# circuit.net
KiCad netlist of a schematic drawn in EAGLE
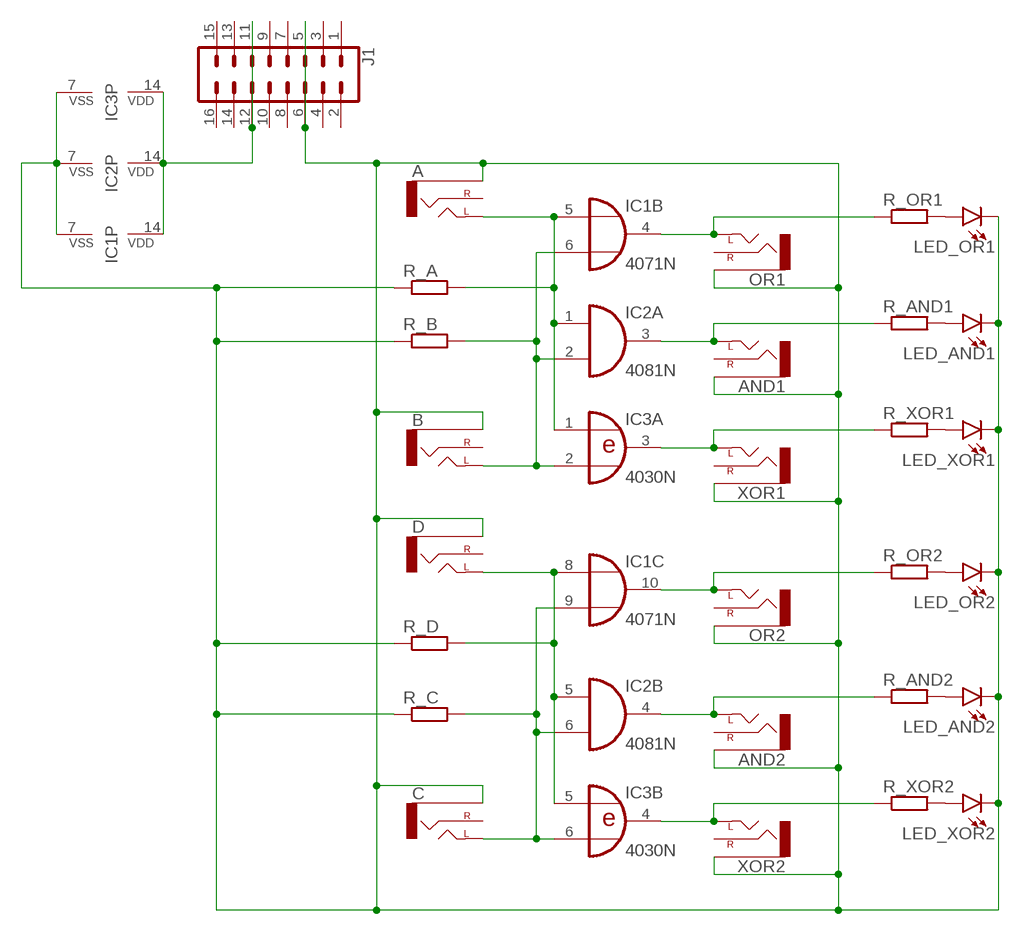
[diagram p0: schematic, sheet 1]

(export (version "E")
  (design (tool "Eeschema 10.0.6"))
  (components
    (comp (ref "A")
      (value "THONKI-STEREO")
      (footprint "eagle-import:WQP-PJ366ST_JACK")
      (libsource (lib "eagle-import") (part "THONKI-STEREO"))
    )
    (comp (ref "AND1")
      (value "THONKI-STEREO")
      (footprint "eagle-import:WQP-PJ366ST_JACK")
      (libsource (lib "eagle-import") (part "THONKI-STEREO"))
    )
    (comp (ref "AND2")
      (value "THONKI-STEREO")
      (footprint "eagle-import:WQP-PJ366ST_JACK")
      (libsource (lib "eagle-import") (part "THONKI-STEREO"))
    )
    (comp (ref "B")
      (value "THONKI-STEREO")
      (footprint "eagle-import:WQP-PJ366ST_JACK")
      (libsource (lib "eagle-import") (part "THONKI-STEREO"))
    )
    (comp (ref "C")
      (value "THONKI-STEREO")
      (footprint "eagle-import:WQP-PJ366ST_JACK")
      (libsource (lib "eagle-import") (part "THONKI-STEREO"))
    )
    (comp (ref "D")
      (value "THONKI-STEREO")
      (footprint "eagle-import:WQP-PJ366ST_JACK")
      (libsource (lib "eagle-import") (part "THONKI-STEREO"))
    )
    (comp (ref "IC1")
      (value "4071N")
      (footprint "eagle-import:DIL14")
      (libsource (lib "eagle-import") (part "4071N"))
    )
    (comp (ref "IC2")
      (value "4081N")
      (footprint "eagle-import:DIL14")
      (libsource (lib "eagle-import") (part "4081N"))
    )
    (comp (ref "IC3")
      (value "4030N")
      (footprint "eagle-import:DIL14")
      (libsource (lib "eagle-import") (part "4030N"))
    )
    (comp (ref "J1")
      (value "CONN_08X2")
      (footprint "eagle-import:2X8")
      (libsource (lib "eagle-import") (part "CONN_08X2"))
    )
    (comp (ref "LED_AND1")
      (value "LED3MM")
      (footprint "eagle-import:LED_3MM")
      (libsource (lib "eagle-import") (part "LED3MM"))
    )
    (comp (ref "LED_AND2")
      (value "LED3MM")
      (footprint "eagle-import:LED_3MM")
      (libsource (lib "eagle-import") (part "LED3MM"))
    )
    (comp (ref "LED_OR1")
      (value "LED3MM")
      (footprint "eagle-import:LED_3MM")
      (libsource (lib "eagle-import") (part "LED3MM"))
    )
    (comp (ref "LED_OR2")
      (value "LED3MM")
      (footprint "eagle-import:LED_3MM")
      (libsource (lib "eagle-import") (part "LED3MM"))
    )
    (comp (ref "LED_XOR1")
      (value "LED3MM")
      (footprint "eagle-import:LED_3MM")
      (libsource (lib "eagle-import") (part "LED3MM"))
    )
    (comp (ref "LED_XOR2")
      (value "LED3MM")
      (footprint "eagle-import:LED_3MM")
      (libsource (lib "eagle-import") (part "LED3MM"))
    )
    (comp (ref "OR1")
      (value "THONKI-STEREO")
      (footprint "eagle-import:WQP-PJ366ST_JACK")
      (libsource (lib "eagle-import") (part "THONKI-STEREO"))
    )
    (comp (ref "OR2")
      (value "THONKI-STEREO")
      (footprint "eagle-import:WQP-PJ366ST_JACK")
      (libsource (lib "eagle-import") (part "THONKI-STEREO"))
    )
    (comp (ref "R_A")
      (value "RESISTOR7MM")
      (footprint "eagle-import:7MM_RESISTOR")
      (libsource (lib "eagle-import") (part "RESISTOR7MM"))
    )
    (comp (ref "R_AND1")
      (value "RESISTOR7MM")
      (footprint "eagle-import:7MM_RESISTOR")
      (libsource (lib "eagle-import") (part "RESISTOR7MM"))
    )
    (comp (ref "R_AND2")
      (value "RESISTOR7MM")
      (footprint "eagle-import:7MM_RESISTOR")
      (libsource (lib "eagle-import") (part "RESISTOR7MM"))
    )
    (comp (ref "R_B")
      (value "RESISTOR7MM")
      (footprint "eagle-import:7MM_RESISTOR")
      (libsource (lib "eagle-import") (part "RESISTOR7MM"))
    )
    (comp (ref "R_C")
      (value "RESISTOR7MM")
      (footprint "eagle-import:7MM_RESISTOR")
      (libsource (lib "eagle-import") (part "RESISTOR7MM"))
    )
    (comp (ref "R_D")
      (value "RESISTOR7MM")
      (footprint "eagle-import:7MM_RESISTOR")
      (libsource (lib "eagle-import") (part "RESISTOR7MM"))
    )
    (comp (ref "R_OR1")
      (value "RESISTOR7MM")
      (footprint "eagle-import:7MM_RESISTOR")
      (libsource (lib "eagle-import") (part "RESISTOR7MM"))
    )
    (comp (ref "R_OR2")
      (value "RESISTOR7MM")
      (footprint "eagle-import:7MM_RESISTOR")
      (libsource (lib "eagle-import") (part "RESISTOR7MM"))
    )
    (comp (ref "R_XOR1")
      (value "RESISTOR7MM")
      (footprint "eagle-import:7MM_RESISTOR")
      (libsource (lib "eagle-import") (part "RESISTOR7MM"))
    )
    (comp (ref "R_XOR2")
      (value "RESISTOR7MM")
      (footprint "eagle-import:7MM_RESISTOR")
      (libsource (lib "eagle-import") (part "RESISTOR7MM"))
    )
    (comp (ref "XOR1")
      (value "THONKI-STEREO")
      (footprint "eagle-import:WQP-PJ366ST_JACK")
      (libsource (lib "eagle-import") (part "THONKI-STEREO"))
    )
    (comp (ref "XOR2")
      (value "THONKI-STEREO")
      (footprint "eagle-import:WQP-PJ366ST_JACK")
      (libsource (lib "eagle-import") (part "THONKI-STEREO"))
    )
  )
  (nets
    (net (code "1") (name "Net-(A-LEFT)") (class "Default")
      (node (ref "A") (pin "P$1_TIP") (pinfunction "LEFT_P$1_TIP") (pintype "bidirectional"))
      (node (ref "IC1") (pin "5") (pinfunction "I0_5") (pintype "input"))
      (node (ref "IC2") (pin "1") (pinfunction "I0_1") (pintype "input"))
      (node (ref "IC3") (pin "1") (pinfunction "I0_1") (pintype "input"))
      (node (ref "R_A") (pin "2") (pinfunction "2_2") (pintype "passive"))
    )
    (net (code "2") (name "Net-(A-SLEEVE)") (class "Default")
      (node (ref "A") (pin "P$3_SLEEVE") (pinfunction "SLEEVE_P$3_SLEEVE") (pintype "bidirectional"))
      (node (ref "AND1") (pin "P$3_SLEEVE") (pinfunction "SLEEVE_P$3_SLEEVE") (pintype "bidirectional"))
      (node (ref "AND2") (pin "P$3_SLEEVE") (pinfunction "SLEEVE_P$3_SLEEVE") (pintype "bidirectional"))
      (node (ref "B") (pin "P$3_SLEEVE") (pinfunction "SLEEVE_P$3_SLEEVE") (pintype "bidirectional"))
      (node (ref "C") (pin "P$3_SLEEVE") (pinfunction "SLEEVE_P$3_SLEEVE") (pintype "bidirectional"))
      (node (ref "D") (pin "P$3_SLEEVE") (pinfunction "SLEEVE_P$3_SLEEVE") (pintype "bidirectional"))
      (node (ref "IC1") (pin "7") (pinfunction "VSS_7") (pintype "power_in"))
      (node (ref "IC2") (pin "7") (pinfunction "VSS_7") (pintype "power_in"))
      (node (ref "IC3") (pin "7") (pinfunction "VSS_7") (pintype "power_in"))
      (node (ref "J1") (pin "5") (pinfunction "5_5") (pintype "passive"))
      (node (ref "J1") (pin "6") (pinfunction "6_6") (pintype "passive"))
      (node (ref "LED_AND1") (pin "K") (pinfunction "C_K") (pintype "passive"))
      (node (ref "LED_AND2") (pin "K") (pinfunction "C_K") (pintype "passive"))
      (node (ref "LED_OR1") (pin "K") (pinfunction "C_K") (pintype "passive"))
      (node (ref "LED_OR2") (pin "K") (pinfunction "C_K") (pintype "passive"))
      (node (ref "LED_XOR1") (pin "K") (pinfunction "C_K") (pintype "passive"))
      (node (ref "LED_XOR2") (pin "K") (pinfunction "C_K") (pintype "passive"))
      (node (ref "OR1") (pin "P$3_SLEEVE") (pinfunction "SLEEVE_P$3_SLEEVE") (pintype "bidirectional"))
      (node (ref "OR2") (pin "P$3_SLEEVE") (pinfunction "SLEEVE_P$3_SLEEVE") (pintype "bidirectional"))
      (node (ref "R_A") (pin "1") (pinfunction "1_1") (pintype "passive"))
      (node (ref "R_B") (pin "1") (pinfunction "1_1") (pintype "passive"))
      (node (ref "R_C") (pin "1") (pinfunction "1_1") (pintype "passive"))
      (node (ref "R_D") (pin "1") (pinfunction "1_1") (pintype "passive"))
      (node (ref "XOR1") (pin "P$3_SLEEVE") (pinfunction "SLEEVE_P$3_SLEEVE") (pintype "bidirectional"))
      (node (ref "XOR2") (pin "P$3_SLEEVE") (pinfunction "SLEEVE_P$3_SLEEVE") (pintype "bidirectional"))
    )
    (net (code "3") (name "Net-(AND1-LEFT)") (class "Default")
      (node (ref "AND1") (pin "P$1_TIP") (pinfunction "LEFT_P$1_TIP") (pintype "bidirectional"))
      (node (ref "IC2") (pin "3") (pinfunction "O_3") (pintype "output"))
      (node (ref "R_AND1") (pin "1") (pinfunction "1_1") (pintype "passive"))
    )
    (net (code "4") (name "Net-(AND2-LEFT)") (class "Default")
      (node (ref "AND2") (pin "P$1_TIP") (pinfunction "LEFT_P$1_TIP") (pintype "bidirectional"))
      (node (ref "IC2") (pin "4") (pinfunction "O_4") (pintype "output"))
      (node (ref "R_AND2") (pin "1") (pinfunction "1_1") (pintype "passive"))
    )
    (net (code "5") (name "Net-(B-LEFT)") (class "Default")
      (node (ref "B") (pin "P$1_TIP") (pinfunction "LEFT_P$1_TIP") (pintype "bidirectional"))
      (node (ref "IC1") (pin "6") (pinfunction "I1_6") (pintype "input"))
      (node (ref "IC2") (pin "2") (pinfunction "I1_2") (pintype "input"))
      (node (ref "IC3") (pin "2") (pinfunction "I1_2") (pintype "input"))
      (node (ref "R_B") (pin "2") (pinfunction "2_2") (pintype "passive"))
    )
    (net (code "6") (name "Net-(C-LEFT)") (class "Default")
      (node (ref "C") (pin "P$1_TIP") (pinfunction "LEFT_P$1_TIP") (pintype "bidirectional"))
      (node (ref "IC1") (pin "9") (pinfunction "I1_9") (pintype "input"))
      (node (ref "IC2") (pin "6") (pinfunction "I1_6") (pintype "input"))
      (node (ref "IC3") (pin "6") (pinfunction "I1_6") (pintype "input"))
      (node (ref "R_C") (pin "2") (pinfunction "2_2") (pintype "passive"))
    )
    (net (code "7") (name "Net-(D-LEFT)") (class "Default")
      (node (ref "D") (pin "P$1_TIP") (pinfunction "LEFT_P$1_TIP") (pintype "bidirectional"))
      (node (ref "IC1") (pin "8") (pinfunction "I0_8") (pintype "input"))
      (node (ref "IC2") (pin "5") (pinfunction "I0_5") (pintype "input"))
      (node (ref "IC3") (pin "5") (pinfunction "I0_5") (pintype "input"))
      (node (ref "R_D") (pin "2") (pinfunction "2_2") (pintype "passive"))
    )
    (net (code "8") (name "Net-(IC1B-O)") (class "Default")
      (node (ref "IC1") (pin "4") (pinfunction "O_4") (pintype "output"))
      (node (ref "OR1") (pin "P$1_TIP") (pinfunction "LEFT_P$1_TIP") (pintype "bidirectional"))
      (node (ref "R_OR1") (pin "1") (pinfunction "1_1") (pintype "passive"))
    )
    (net (code "9") (name "Net-(IC1C-O)") (class "Default")
      (node (ref "IC1") (pin "10") (pinfunction "O_10") (pintype "output"))
      (node (ref "OR2") (pin "P$1_TIP") (pinfunction "LEFT_P$1_TIP") (pintype "bidirectional"))
      (node (ref "R_OR2") (pin "1") (pinfunction "1_1") (pintype "passive"))
    )
    (net (code "10") (name "Net-(IC1E-VDD)") (class "Default")
      (node (ref "IC1") (pin "14") (pinfunction "VDD_14") (pintype "power_in"))
      (node (ref "IC2") (pin "14") (pinfunction "VDD_14") (pintype "power_in"))
      (node (ref "IC3") (pin "14") (pinfunction "VDD_14") (pintype "power_in"))
      (node (ref "J1") (pin "11") (pinfunction "11_11") (pintype "passive"))
      (node (ref "J1") (pin "12") (pinfunction "12_12") (pintype "passive"))
    )
    (net (code "11") (name "Net-(IC3A-O)") (class "Default")
      (node (ref "IC3") (pin "3") (pinfunction "O_3") (pintype "output"))
      (node (ref "R_XOR1") (pin "1") (pinfunction "1_1") (pintype "passive"))
      (node (ref "XOR1") (pin "P$1_TIP") (pinfunction "LEFT_P$1_TIP") (pintype "bidirectional"))
    )
    (net (code "12") (name "Net-(IC3B-O)") (class "Default")
      (node (ref "IC3") (pin "4") (pinfunction "O_4") (pintype "output"))
      (node (ref "R_XOR2") (pin "1") (pinfunction "1_1") (pintype "passive"))
      (node (ref "XOR2") (pin "P$1_TIP") (pinfunction "LEFT_P$1_TIP") (pintype "bidirectional"))
    )
    (net (code "13") (name "Net-(LED_AND1-PadA)") (class "Default")
      (node (ref "LED_AND1") (pin "A") (pinfunction "A_A") (pintype "passive"))
      (node (ref "R_AND1") (pin "2") (pinfunction "2_2") (pintype "passive"))
    )
    (net (code "14") (name "Net-(LED_AND2-PadA)") (class "Default")
      (node (ref "LED_AND2") (pin "A") (pinfunction "A_A") (pintype "passive"))
      (node (ref "R_AND2") (pin "2") (pinfunction "2_2") (pintype "passive"))
    )
    (net (code "15") (name "Net-(LED_OR1-PadA)") (class "Default")
      (node (ref "LED_OR1") (pin "A") (pinfunction "A_A") (pintype "passive"))
      (node (ref "R_OR1") (pin "2") (pinfunction "2_2") (pintype "passive"))
    )
    (net (code "16") (name "Net-(LED_OR2-PadA)") (class "Default")
      (node (ref "LED_OR2") (pin "A") (pinfunction "A_A") (pintype "passive"))
      (node (ref "R_OR2") (pin "2") (pinfunction "2_2") (pintype "passive"))
    )
    (net (code "17") (name "Net-(LED_XOR1-PadA)") (class "Default")
      (node (ref "LED_XOR1") (pin "A") (pinfunction "A_A") (pintype "passive"))
      (node (ref "R_XOR1") (pin "2") (pinfunction "2_2") (pintype "passive"))
    )
    (net (code "18") (name "Net-(LED_XOR2-PadA)") (class "Default")
      (node (ref "LED_XOR2") (pin "A") (pinfunction "A_A") (pintype "passive"))
      (node (ref "R_XOR2") (pin "2") (pinfunction "2_2") (pintype "passive"))
    )
    (net (code "19") (name "unconnected-(A-RIGHT-PadP$2_SWITCH)") (class "Default")
      (node (ref "A") (pin "P$2_SWITCH") (pinfunction "RIGHT_P$2_SWITCH") (pintype "bidirectional"))
    )
    (net (code "20") (name "unconnected-(AND1-RIGHT-PadP$2_SWITCH)") (class "Default")
      (node (ref "AND1") (pin "P$2_SWITCH") (pinfunction "RIGHT_P$2_SWITCH") (pintype "bidirectional"))
    )
    (net (code "21") (name "unconnected-(AND2-RIGHT-PadP$2_SWITCH)") (class "Default")
      (node (ref "AND2") (pin "P$2_SWITCH") (pinfunction "RIGHT_P$2_SWITCH") (pintype "bidirectional"))
    )
    (net (code "22") (name "unconnected-(B-RIGHT-PadP$2_SWITCH)") (class "Default")
      (node (ref "B") (pin "P$2_SWITCH") (pinfunction "RIGHT_P$2_SWITCH") (pintype "bidirectional"))
    )
    (net (code "23") (name "unconnected-(C-RIGHT-PadP$2_SWITCH)") (class "Default")
      (node (ref "C") (pin "P$2_SWITCH") (pinfunction "RIGHT_P$2_SWITCH") (pintype "bidirectional"))
    )
    (net (code "24") (name "unconnected-(D-RIGHT-PadP$2_SWITCH)") (class "Default")
      (node (ref "D") (pin "P$2_SWITCH") (pinfunction "RIGHT_P$2_SWITCH") (pintype "bidirectional"))
    )
    (net (code "25") (name "unconnected-(J1-Pad1)") (class "Default")
      (node (ref "J1") (pin "1") (pinfunction "1_1") (pintype "passive"))
    )
    (net (code "26") (name "unconnected-(J1-Pad2)") (class "Default")
      (node (ref "J1") (pin "2") (pinfunction "2_2") (pintype "passive"))
    )
    (net (code "27") (name "unconnected-(J1-Pad3)") (class "Default")
      (node (ref "J1") (pin "3") (pinfunction "3_3") (pintype "passive"))
    )
    (net (code "28") (name "unconnected-(J1-Pad4)") (class "Default")
      (node (ref "J1") (pin "4") (pinfunction "4_4") (pintype "passive"))
    )
    (net (code "29") (name "unconnected-(J1-Pad7)") (class "Default")
      (node (ref "J1") (pin "7") (pinfunction "7_7") (pintype "passive"))
    )
    (net (code "30") (name "unconnected-(J1-Pad8)") (class "Default")
      (node (ref "J1") (pin "8") (pinfunction "8_8") (pintype "passive"))
    )
    (net (code "31") (name "unconnected-(J1-Pad9)") (class "Default")
      (node (ref "J1") (pin "9") (pinfunction "9_9") (pintype "passive"))
    )
    (net (code "32") (name "unconnected-(J1-Pad10)") (class "Default")
      (node (ref "J1") (pin "10") (pinfunction "10_10") (pintype "passive"))
    )
    (net (code "33") (name "unconnected-(J1-Pad13)") (class "Default")
      (node (ref "J1") (pin "13") (pinfunction "13_13") (pintype "passive"))
    )
    (net (code "34") (name "unconnected-(J1-Pad14)") (class "Default")
      (node (ref "J1") (pin "14") (pinfunction "14_14") (pintype "passive"))
    )
    (net (code "35") (name "unconnected-(J1-Pad15)") (class "Default")
      (node (ref "J1") (pin "15") (pinfunction "15_15") (pintype "passive"))
    )
    (net (code "36") (name "unconnected-(J1-Pad16)") (class "Default")
      (node (ref "J1") (pin "16") (pinfunction "16_16") (pintype "passive"))
    )
    (net (code "37") (name "unconnected-(OR1-RIGHT-PadP$2_SWITCH)") (class "Default")
      (node (ref "OR1") (pin "P$2_SWITCH") (pinfunction "RIGHT_P$2_SWITCH") (pintype "bidirectional"))
    )
    (net (code "38") (name "unconnected-(OR2-RIGHT-PadP$2_SWITCH)") (class "Default")
      (node (ref "OR2") (pin "P$2_SWITCH") (pinfunction "RIGHT_P$2_SWITCH") (pintype "bidirectional"))
    )
    (net (code "39") (name "unconnected-(XOR1-RIGHT-PadP$2_SWITCH)") (class "Default")
      (node (ref "XOR1") (pin "P$2_SWITCH") (pinfunction "RIGHT_P$2_SWITCH") (pintype "bidirectional"))
    )
    (net (code "40") (name "unconnected-(XOR2-RIGHT-PadP$2_SWITCH)") (class "Default")
      (node (ref "XOR2") (pin "P$2_SWITCH") (pinfunction "RIGHT_P$2_SWITCH") (pintype "bidirectional"))
    )
  )
)
